# SCH_fightpad_2024-06-18.net
KiCad netlist of a schematic drawn in EasyEDA
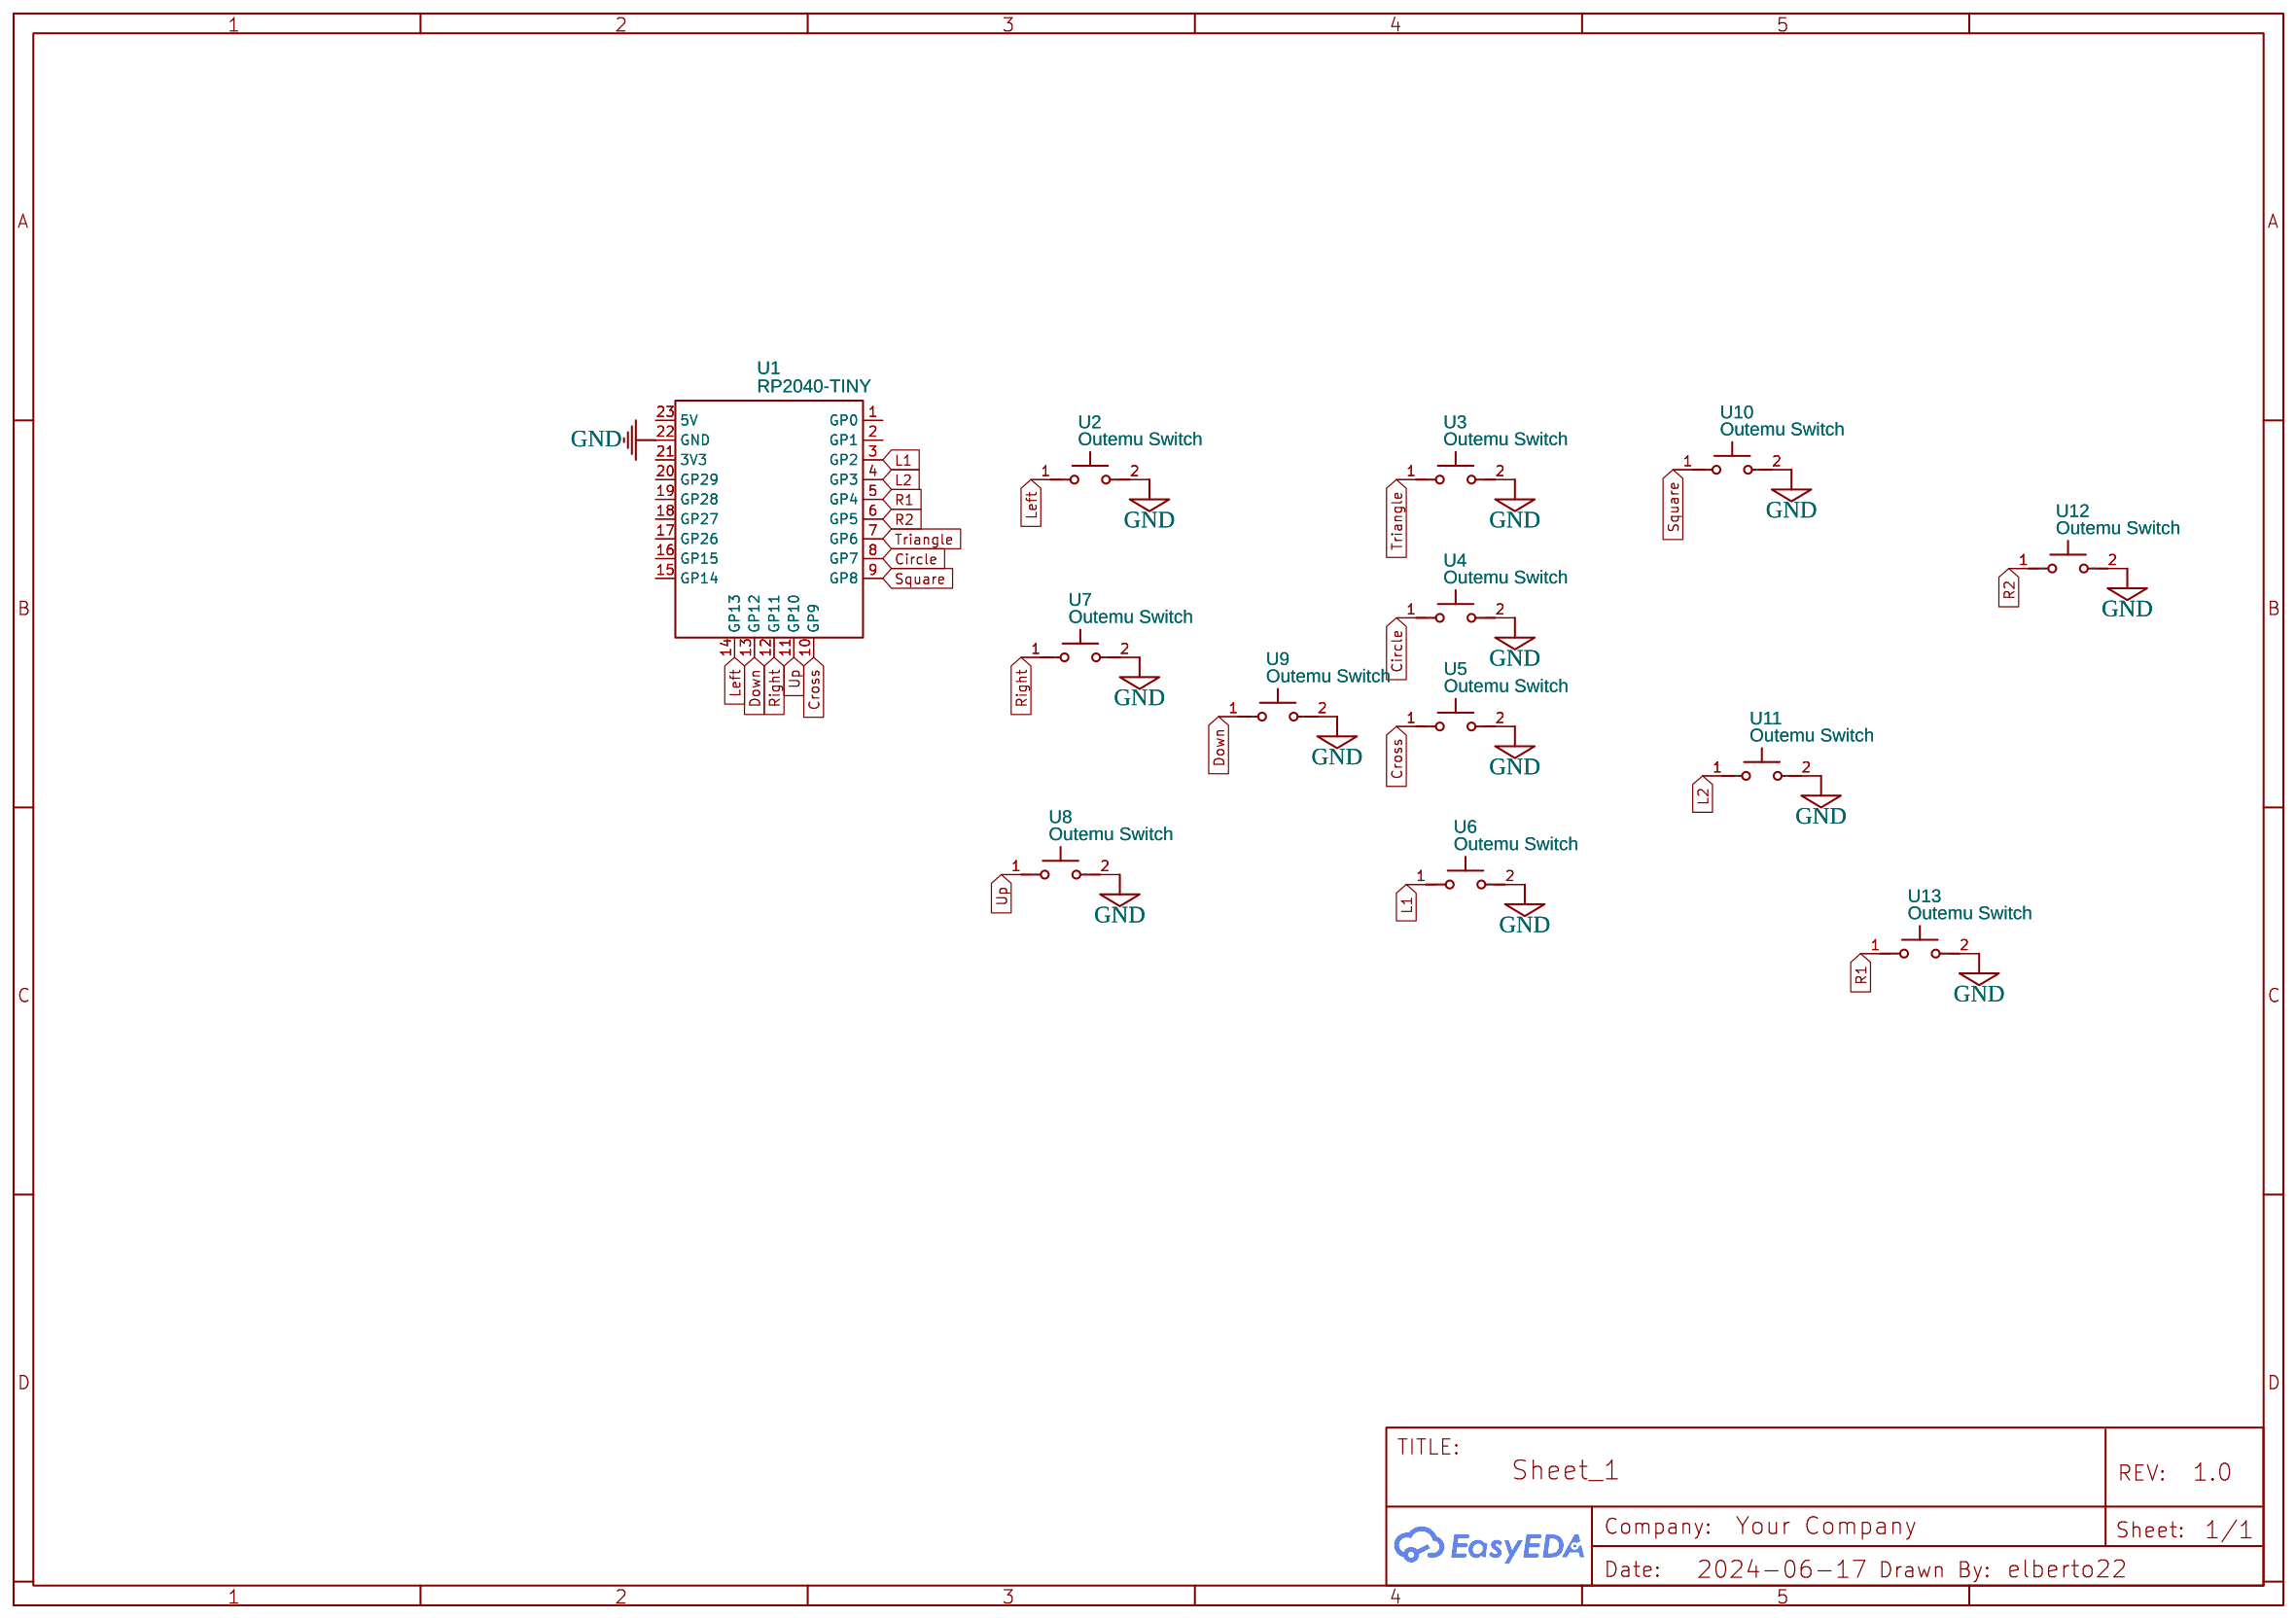
[diagram p0: schematic sheet]

(export (version "E")
  (design (tool "Eeschema 10.0.6"))
  (components
    (comp (ref "U1")
      (value "RP2040-TINY")
      (fields
        (field (name "Manufacturer Part") "RP2040-Tiny")
        (field (name "Manufacturer") "Waveshare(微雪电子)")
      )
      (libsource (lib "") (part "RP2040-TINY"))
    )
    (comp (ref "U2")
      (value "Outemu Switch")
      (fields (field (name "Manufacturer") "HepLer"))
      (libsource (lib "") (part "Outemu Switch"))
    )
    (comp (ref "U3")
      (value "Outemu Switch")
      (fields (field (name "Manufacturer") "HepLer"))
      (libsource (lib "") (part "Outemu Switch"))
    )
    (comp (ref "U4")
      (value "Outemu Switch")
      (fields (field (name "Manufacturer") "HepLer"))
      (libsource (lib "") (part "Outemu Switch"))
    )
    (comp (ref "U5")
      (value "Outemu Switch")
      (fields (field (name "Manufacturer") "HepLer"))
      (libsource (lib "") (part "Outemu Switch"))
    )
    (comp (ref "U6")
      (value "Outemu Switch")
      (fields (field (name "Manufacturer") "HepLer"))
      (libsource (lib "") (part "Outemu Switch"))
    )
    (comp (ref "U7")
      (value "Outemu Switch")
      (fields (field (name "Manufacturer") "HepLer"))
      (libsource (lib "") (part "Outemu Switch"))
    )
    (comp (ref "U8")
      (value "Outemu Switch")
      (fields (field (name "Manufacturer") "HepLer"))
      (libsource (lib "") (part "Outemu Switch"))
    )
    (comp (ref "U9")
      (value "Outemu Switch")
      (fields (field (name "Manufacturer") "HepLer"))
      (libsource (lib "") (part "Outemu Switch"))
    )
    (comp (ref "U10")
      (value "Outemu Switch")
      (fields (field (name "Manufacturer") "HepLer"))
      (libsource (lib "") (part "Outemu Switch"))
    )
    (comp (ref "U11")
      (value "Outemu Switch")
      (fields (field (name "Manufacturer") "HepLer"))
      (libsource (lib "") (part "Outemu Switch"))
    )
    (comp (ref "U12")
      (value "Outemu Switch")
      (fields (field (name "Manufacturer") "HepLer"))
      (libsource (lib "") (part "Outemu Switch"))
    )
    (comp (ref "U13")
      (value "Outemu Switch")
      (fields (field (name "Manufacturer") "HepLer"))
      (libsource (lib "") (part "Outemu Switch"))
    )
  )
  (nets
    (net (code "1") (name "Circle") (class "Default")
      (node (ref "U1") (pin "8") (pinfunction "GP7_8") (pintype "unspecified"))
      (node (ref "U4") (pin "1") (pinfunction "1_1") (pintype "unspecified"))
    )
    (net (code "2") (name "Cross") (class "Default")
      (node (ref "U1") (pin "10") (pinfunction "GP9_10") (pintype "unspecified"))
      (node (ref "U5") (pin "1") (pinfunction "1_1") (pintype "unspecified"))
    )
    (net (code "3") (name "Down") (class "Default")
      (node (ref "U1") (pin "13") (pinfunction "GP12_13") (pintype "unspecified"))
      (node (ref "U9") (pin "1") (pinfunction "1_1") (pintype "unspecified"))
    )
    (net (code "4") (name "GND") (class "Default")
      (node (ref "U1") (pin "22") (pinfunction "GND_22") (pintype "unspecified"))
      (node (ref "U10") (pin "2") (pinfunction "2_2") (pintype "unspecified"))
      (node (ref "U11") (pin "2") (pinfunction "2_2") (pintype "unspecified"))
      (node (ref "U12") (pin "2") (pinfunction "2_2") (pintype "unspecified"))
      (node (ref "U13") (pin "2") (pinfunction "2_2") (pintype "unspecified"))
      (node (ref "U2") (pin "2") (pinfunction "2_2") (pintype "unspecified"))
      (node (ref "U3") (pin "2") (pinfunction "2_2") (pintype "unspecified"))
      (node (ref "U4") (pin "2") (pinfunction "2_2") (pintype "unspecified"))
      (node (ref "U5") (pin "2") (pinfunction "2_2") (pintype "unspecified"))
      (node (ref "U6") (pin "2") (pinfunction "2_2") (pintype "unspecified"))
      (node (ref "U7") (pin "2") (pinfunction "2_2") (pintype "unspecified"))
      (node (ref "U8") (pin "2") (pinfunction "2_2") (pintype "unspecified"))
      (node (ref "U9") (pin "2") (pinfunction "2_2") (pintype "unspecified"))
    )
    (net (code "5") (name "L1") (class "Default")
      (node (ref "U1") (pin "3") (pinfunction "GP2_3") (pintype "unspecified"))
      (node (ref "U6") (pin "1") (pinfunction "1_1") (pintype "unspecified"))
    )
    (net (code "6") (name "L2") (class "Default")
      (node (ref "U1") (pin "4") (pinfunction "GP3_4") (pintype "unspecified"))
      (node (ref "U11") (pin "1") (pinfunction "1_1") (pintype "unspecified"))
    )
    (net (code "7") (name "Left") (class "Default")
      (node (ref "U1") (pin "14") (pinfunction "GP13_14") (pintype "unspecified"))
      (node (ref "U2") (pin "1") (pinfunction "1_1") (pintype "unspecified"))
    )
    (net (code "8") (name "R1") (class "Default")
      (node (ref "U1") (pin "5") (pinfunction "GP4_5") (pintype "unspecified"))
      (node (ref "U13") (pin "1") (pinfunction "1_1") (pintype "unspecified"))
    )
    (net (code "9") (name "R2") (class "Default")
      (node (ref "U1") (pin "6") (pinfunction "GP5_6") (pintype "unspecified"))
      (node (ref "U12") (pin "1") (pinfunction "1_1") (pintype "unspecified"))
    )
    (net (code "10") (name "Right") (class "Default")
      (node (ref "U1") (pin "12") (pinfunction "GP11_12") (pintype "unspecified"))
      (node (ref "U7") (pin "1") (pinfunction "1_1") (pintype "unspecified"))
    )
    (net (code "11") (name "Square") (class "Default")
      (node (ref "U1") (pin "9") (pinfunction "GP8_9") (pintype "unspecified"))
      (node (ref "U10") (pin "1") (pinfunction "1_1") (pintype "unspecified"))
    )
    (net (code "12") (name "Triangle") (class "Default")
      (node (ref "U1") (pin "7") (pinfunction "GP6_7") (pintype "unspecified"))
      (node (ref "U3") (pin "1") (pinfunction "1_1") (pintype "unspecified"))
    )
    (net (code "13") (name "Up") (class "Default")
      (node (ref "U1") (pin "11") (pinfunction "GP10_11") (pintype "unspecified"))
      (node (ref "U8") (pin "1") (pinfunction "1_1") (pintype "unspecified"))
    )
    (net (code "14") (name "unconnected-(U1-3V3-Pad21)") (class "Default")
      (node (ref "U1") (pin "21") (pinfunction "3V3_21") (pintype "unspecified"))
    )
    (net (code "15") (name "unconnected-(U1-5V-Pad23)") (class "Default")
      (node (ref "U1") (pin "23") (pinfunction "5V_23") (pintype "unspecified"))
    )
    (net (code "16") (name "unconnected-(U1-GP0-Pad1)") (class "Default")
      (node (ref "U1") (pin "1") (pinfunction "GP0_1") (pintype "unspecified"))
    )
    (net (code "17") (name "unconnected-(U1-GP1-Pad2)") (class "Default")
      (node (ref "U1") (pin "2") (pinfunction "GP1_2") (pintype "unspecified"))
    )
    (net (code "18") (name "unconnected-(U1-GP14-Pad15)") (class "Default")
      (node (ref "U1") (pin "15") (pinfunction "GP14_15") (pintype "unspecified"))
    )
    (net (code "19") (name "unconnected-(U1-GP15-Pad16)") (class "Default")
      (node (ref "U1") (pin "16") (pinfunction "GP15_16") (pintype "unspecified"))
    )
    (net (code "20") (name "unconnected-(U1-GP26-Pad17)") (class "Default")
      (node (ref "U1") (pin "17") (pinfunction "GP26_17") (pintype "unspecified"))
    )
    (net (code "21") (name "unconnected-(U1-GP27-Pad18)") (class "Default")
      (node (ref "U1") (pin "18") (pinfunction "GP27_18") (pintype "unspecified"))
    )
    (net (code "22") (name "unconnected-(U1-GP28-Pad19)") (class "Default")
      (node (ref "U1") (pin "19") (pinfunction "GP28_19") (pintype "unspecified"))
    )
    (net (code "23") (name "unconnected-(U1-GP29-Pad20)") (class "Default")
      (node (ref "U1") (pin "20") (pinfunction "GP29_20") (pintype "unspecified"))
    )
  )
)
